# E3-Touch_Sensor_v1.net
KiCad netlist of a schematic drawn in EAGLE
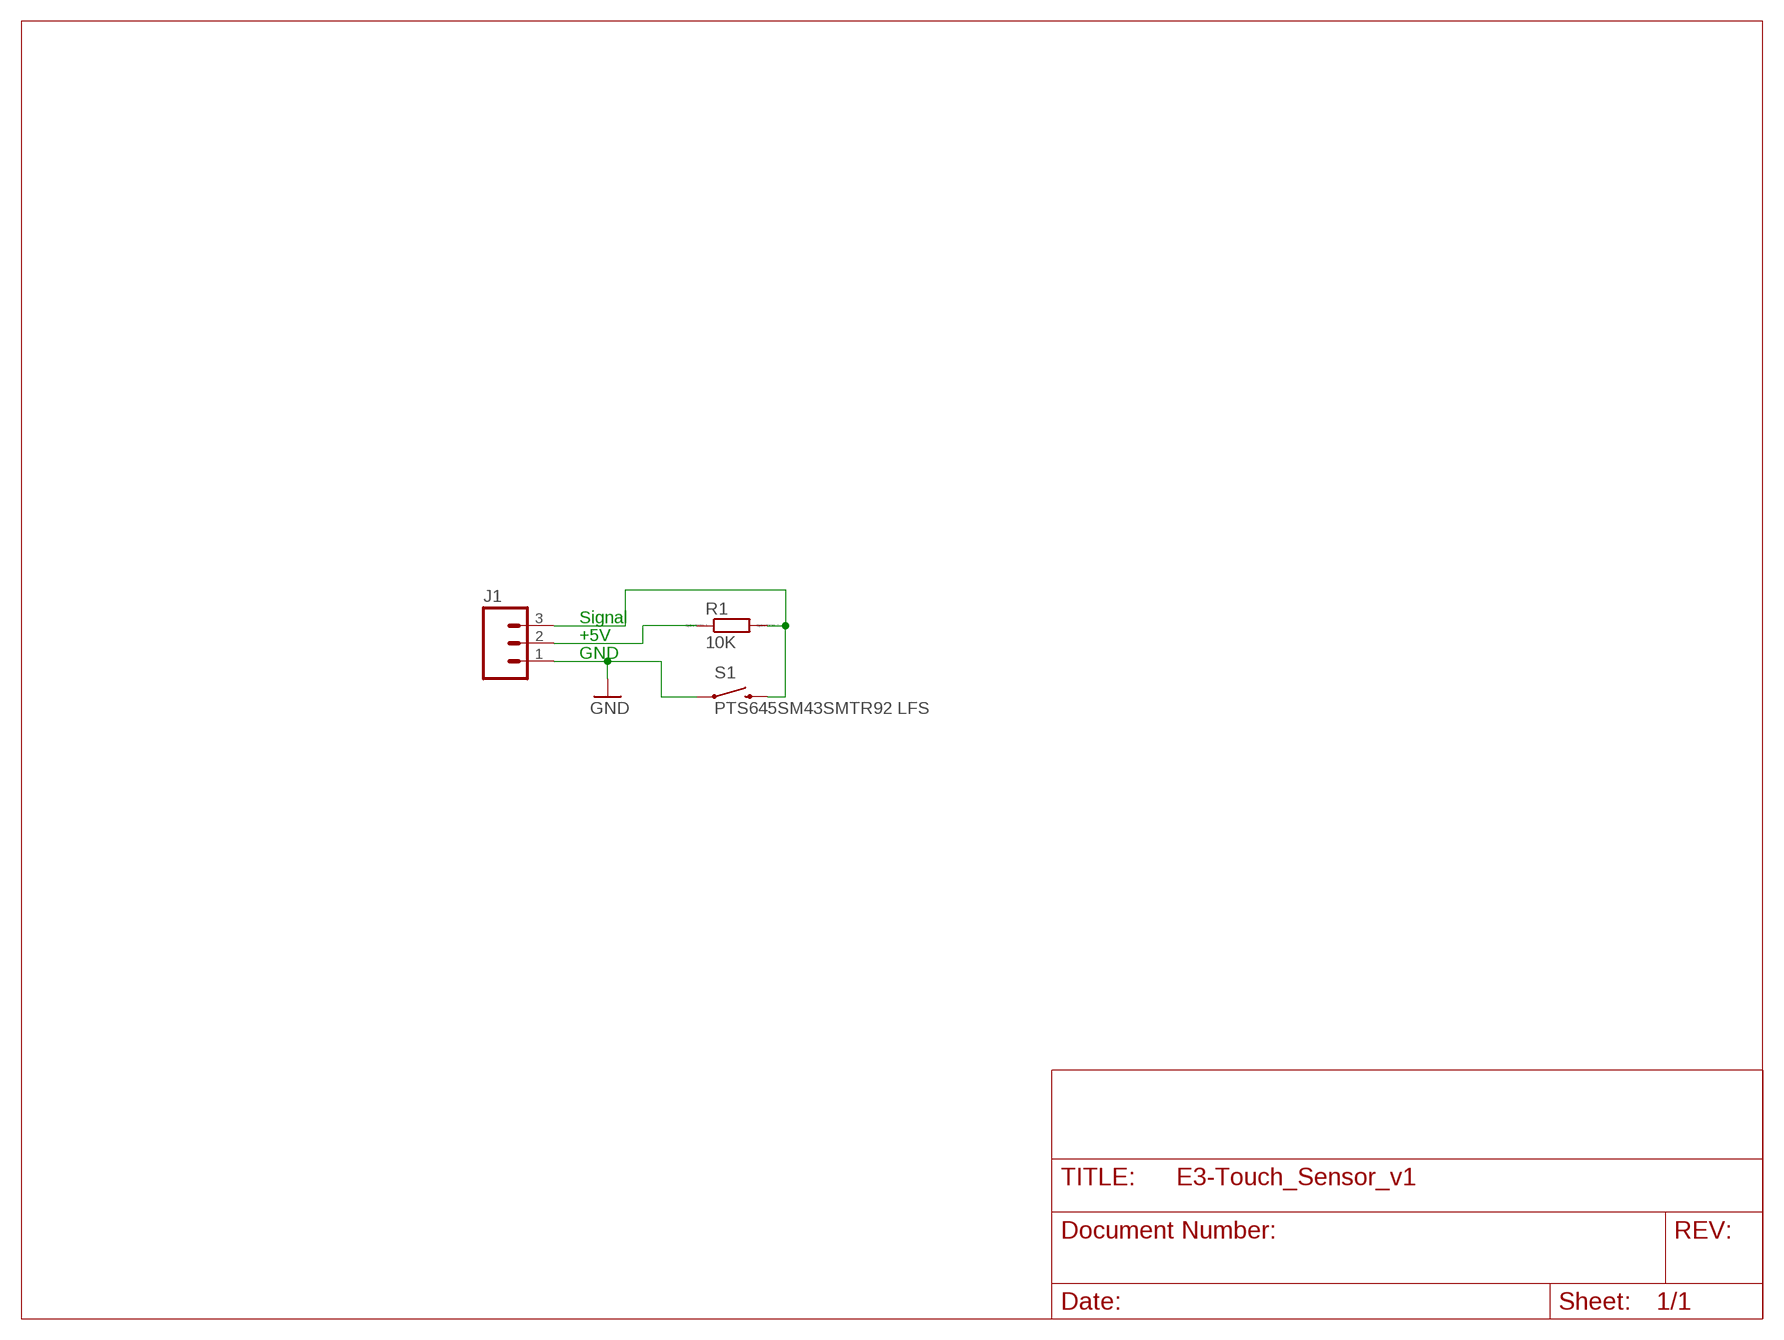
[diagram p0: schematic, sheet 1]

(export (version "E")
  (design (tool "Eeschema 10.0.6"))
  (components
    (comp (ref "J1")
      (value "M03PTH")
      (footprint "eagle-import:1X03")
      (libsource (lib "eagle-import") (part "M03PTH"))
    )
    (comp (ref "R1")
      (value "10K")
      (footprint "eagle-import:R0603")
      (libsource (lib "eagle-import") (part "RR0603"))
    )
    (comp (ref "S1")
      (value "PTS645SM43SMTR92 LFS")
      (footprint "eagle-import:TACTILE_SWITCH_TALL")
      (libsource (lib "eagle-import") (part "SWITCH-MOMENTARY-2SMD-4"))
    )
  )
  (nets
    (net (code "1") (name "GND") (class "Default")
      (node (ref "J1") (pin "1") (pinfunction "1_1") (pintype "passive"))
      (node (ref "S1") (pin "A2") (pinfunction "1_A2") (pintype "passive"))
    )
    (net (code "2") (name "Net-(J1-Pad2)") (class "Default")
      (node (ref "J1") (pin "2") (pinfunction "2_2") (pintype "passive"))
      (node (ref "R1") (pin "1") (pinfunction "1_1") (pintype "passive"))
    )
    (net (code "3") (name "Net-(S1-2)") (class "Default")
      (node (ref "J1") (pin "3") (pinfunction "3_3") (pintype "passive"))
      (node (ref "R1") (pin "2") (pinfunction "2_2") (pintype "passive"))
      (node (ref "S1") (pin "B2") (pinfunction "2_B2") (pintype "passive"))
    )
  )
)
